# ATTinyKnob.net
KiCad netlist of a schematic drawn in EAGLE
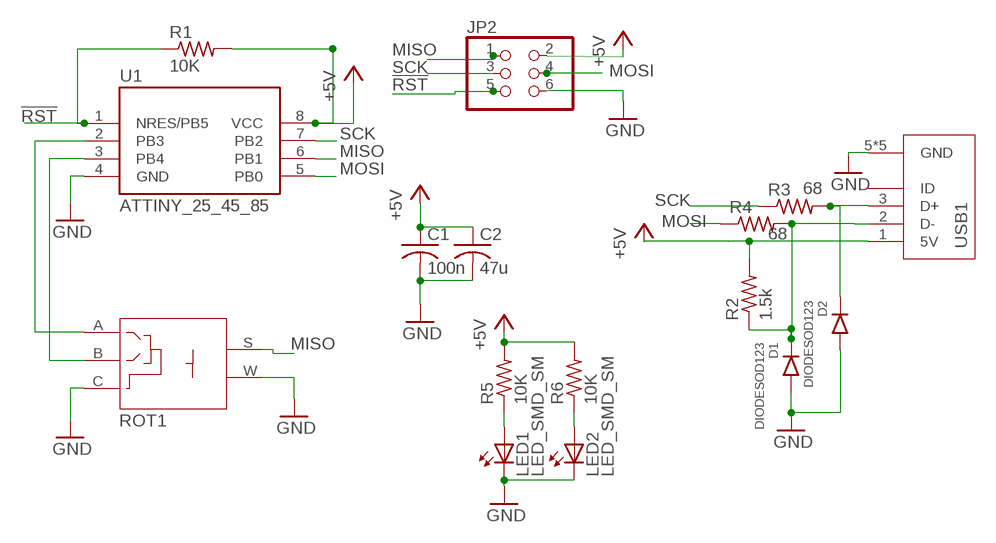
[diagram p0: schematic, sheet 1]

(export (version "E")
  (design (tool "Eeschema 10.0.6"))
  (components
    (comp (ref "C1")
      (value "100n")
      (footprint "eagle-import:C0805")
      (libsource (lib "eagle-import") (part "C-USC0805"))
    )
    (comp (ref "C2")
      (value "47u")
      (footprint "eagle-import:C0805")
      (libsource (lib "eagle-import") (part "C-USC0805"))
    )
    (comp (ref "D1")
      (value "DIODESOD123")
      (footprint "eagle-import:SOD123")
      (libsource (lib "eagle-import") (part "DIODESOD123"))
    )
    (comp (ref "D2")
      (value "DIODESOD123")
      (footprint "eagle-import:SOD123")
      (libsource (lib "eagle-import") (part "DIODESOD123"))
    )
    (comp (ref "JP2")
      (value "PINHD-2X3")
      (footprint "eagle-import:2X03")
      (libsource (lib "eagle-import") (part "PINHD-2X3"))
    )
    (comp (ref "LED1")
      (value "LED_SMD_SM")
      (footprint "eagle-import:LED_SMD_SM")
      (libsource (lib "eagle-import") (part "LED_SMD_SM"))
    )
    (comp (ref "LED2")
      (value "LED_SMD_SM")
      (footprint "eagle-import:LED_SMD_SM")
      (libsource (lib "eagle-import") (part "LED_SMD_SM"))
    )
    (comp (ref "R1")
      (value "10K")
      (footprint "eagle-import:M1206")
      (libsource (lib "eagle-import") (part "R-US_M1206"))
    )
    (comp (ref "R2")
      (value "1.5k")
      (footprint "eagle-import:M1206")
      (libsource (lib "eagle-import") (part "R-US_M1206"))
    )
    (comp (ref "R3")
      (value "68")
      (footprint "eagle-import:M1206")
      (libsource (lib "eagle-import") (part "R-US_M1206"))
    )
    (comp (ref "R4")
      (value "68")
      (footprint "eagle-import:M1206")
      (libsource (lib "eagle-import") (part "R-US_M1206"))
    )
    (comp (ref "R5")
      (value "10K")
      (footprint "eagle-import:M1206")
      (libsource (lib "eagle-import") (part "R-US_M1206"))
    )
    (comp (ref "R6")
      (value "10K")
      (footprint "eagle-import:M1206")
      (libsource (lib "eagle-import") (part "R-US_M1206"))
    )
    (comp (ref "ROT1")
      (value "ROTARY_EC16")
      (footprint "eagle-import:ROTARY_EC16")
      (libsource (lib "eagle-import") (part "ROTARY_EC16"))
    )
    (comp (ref "U1")
      (value "ATTINY_25_45_85")
      (footprint "eagle-import:SOIC-8")
      (libsource (lib "eagle-import") (part "ATTINY_25_45_85"))
    )
    (comp (ref "USB1")
      (value "USB_MINIUSB_MINI_TH_RIGHTANG")
      (footprint "eagle-import:USB_MINI_TH_RIGHTANGLE")
      (libsource (lib "eagle-import") (part "USB_MINIUSB_MINI_TH_RIGHTANG"))
    )
  )
  (nets
    (net (code "1") (name "+5V") (class "Default")
      (node (ref "C1") (pin "1") (pinfunction "1_1") (pintype "passive"))
      (node (ref "C2") (pin "1") (pinfunction "1_1") (pintype "passive"))
      (node (ref "JP2") (pin "2") (pinfunction "2_2") (pintype "passive"))
      (node (ref "R1") (pin "2") (pinfunction "2_2") (pintype "passive"))
      (node (ref "R2") (pin "2") (pinfunction "2_2") (pintype "passive"))
      (node (ref "R5") (pin "2") (pinfunction "2_2") (pintype "passive"))
      (node (ref "R6") (pin "2") (pinfunction "2_2") (pintype "passive"))
      (node (ref "U1") (pin "8") (pinfunction "VCC_8") (pintype "power_in"))
      (node (ref "USB1") (pin "1") (pinfunction "5V_1") (pintype "bidirectional"))
    )
    (net (code "2") (name "/MISO") (class "Default")
      (node (ref "JP2") (pin "1") (pinfunction "1_1") (pintype "passive"))
      (node (ref "ROT1") (pin "S") (pinfunction "S_S") (pintype "bidirectional"))
      (node (ref "U1") (pin "6") (pinfunction "PB1_6") (pintype "bidirectional"))
    )
    (net (code "3") (name "/MOSI") (class "Default")
      (node (ref "JP2") (pin "4") (pinfunction "4_4") (pintype "passive"))
      (node (ref "R4") (pin "1") (pinfunction "1_1") (pintype "passive"))
      (node (ref "U1") (pin "5") (pinfunction "PB0_5") (pintype "bidirectional"))
    )
    (net (code "4") (name "/SCK") (class "Default")
      (node (ref "JP2") (pin "3") (pinfunction "3_3") (pintype "passive"))
      (node (ref "R3") (pin "1") (pinfunction "1_1") (pintype "passive"))
      (node (ref "U1") (pin "7") (pinfunction "PB2_7") (pintype "bidirectional"))
    )
    (net (code "5") (name "/~{RST}") (class "Default")
      (node (ref "JP2") (pin "5") (pinfunction "5_5") (pintype "passive"))
      (node (ref "R1") (pin "1") (pinfunction "1_1") (pintype "passive"))
      (node (ref "U1") (pin "1") (pinfunction "NRES/PB5_1") (pintype "bidirectional"))
    )
    (net (code "6") (name "GND") (class "Default")
      (node (ref "C1") (pin "2") (pinfunction "2_2") (pintype "passive"))
      (node (ref "C2") (pin "2") (pinfunction "2_2") (pintype "passive"))
      (node (ref "D1") (pin "1") (pinfunction "A_1") (pintype "bidirectional"))
      (node (ref "D2") (pin "1") (pinfunction "A_1") (pintype "bidirectional"))
      (node (ref "JP2") (pin "6") (pinfunction "6_6") (pintype "passive"))
      (node (ref "LED1") (pin "2") (pinfunction "C_2") (pintype "passive"))
      (node (ref "LED2") (pin "2") (pinfunction "C_2") (pintype "passive"))
      (node (ref "ROT1") (pin "C") (pinfunction "COM_C") (pintype "bidirectional"))
      (node (ref "ROT1") (pin "W") (pinfunction "W_W") (pintype "bidirectional"))
      (node (ref "U1") (pin "4") (pinfunction "GND_4") (pintype "power_in"))
      (node (ref "USB1") (pin "5") (pinfunction "GND_5") (pintype "bidirectional"))
      (node (ref "USB1") (pin "6") (pinfunction "GND_6") (pintype "bidirectional"))
      (node (ref "USB1") (pin "7") (pinfunction "GND_7") (pintype "bidirectional"))
      (node (ref "USB1") (pin "8") (pinfunction "GND_8") (pintype "bidirectional"))
      (node (ref "USB1") (pin "9") (pinfunction "GND_9") (pintype "bidirectional"))
    )
    (net (code "7") (name "Net-(D1-C)") (class "Default")
      (node (ref "D1") (pin "2") (pinfunction "C_2") (pintype "bidirectional"))
      (node (ref "R2") (pin "1") (pinfunction "1_1") (pintype "passive"))
      (node (ref "R4") (pin "2") (pinfunction "2_2") (pintype "passive"))
      (node (ref "USB1") (pin "2") (pinfunction "D-_2") (pintype "bidirectional"))
    )
    (net (code "8") (name "Net-(D2-C)") (class "Default")
      (node (ref "D2") (pin "2") (pinfunction "C_2") (pintype "bidirectional"))
      (node (ref "R3") (pin "2") (pinfunction "2_2") (pintype "passive"))
      (node (ref "USB1") (pin "3") (pinfunction "D+_3") (pintype "bidirectional"))
    )
    (net (code "9") (name "Net-(LED1-A)") (class "Default")
      (node (ref "LED1") (pin "1") (pinfunction "A_1") (pintype "passive"))
      (node (ref "R5") (pin "1") (pinfunction "1_1") (pintype "passive"))
    )
    (net (code "10") (name "Net-(LED2-A)") (class "Default")
      (node (ref "LED2") (pin "1") (pinfunction "A_1") (pintype "passive"))
      (node (ref "R6") (pin "1") (pinfunction "1_1") (pintype "passive"))
    )
    (net (code "11") (name "Net-(U1-PB3)") (class "Default")
      (node (ref "ROT1") (pin "A") (pinfunction "A_A") (pintype "bidirectional"))
      (node (ref "U1") (pin "2") (pinfunction "PB3_2") (pintype "bidirectional"))
    )
    (net (code "12") (name "Net-(U1-PB4)") (class "Default")
      (node (ref "ROT1") (pin "B") (pinfunction "B_B") (pintype "bidirectional"))
      (node (ref "U1") (pin "3") (pinfunction "PB4_3") (pintype "bidirectional"))
    )
    (net (code "13") (name "unconnected-(USB1-ID-Pad4)") (class "Default")
      (node (ref "USB1") (pin "4") (pinfunction "ID_4") (pintype "bidirectional"))
    )
  )
)
